# GPS_radiologger_v19_LoRa_only.net
KiCad netlist of a schematic drawn in EAGLE
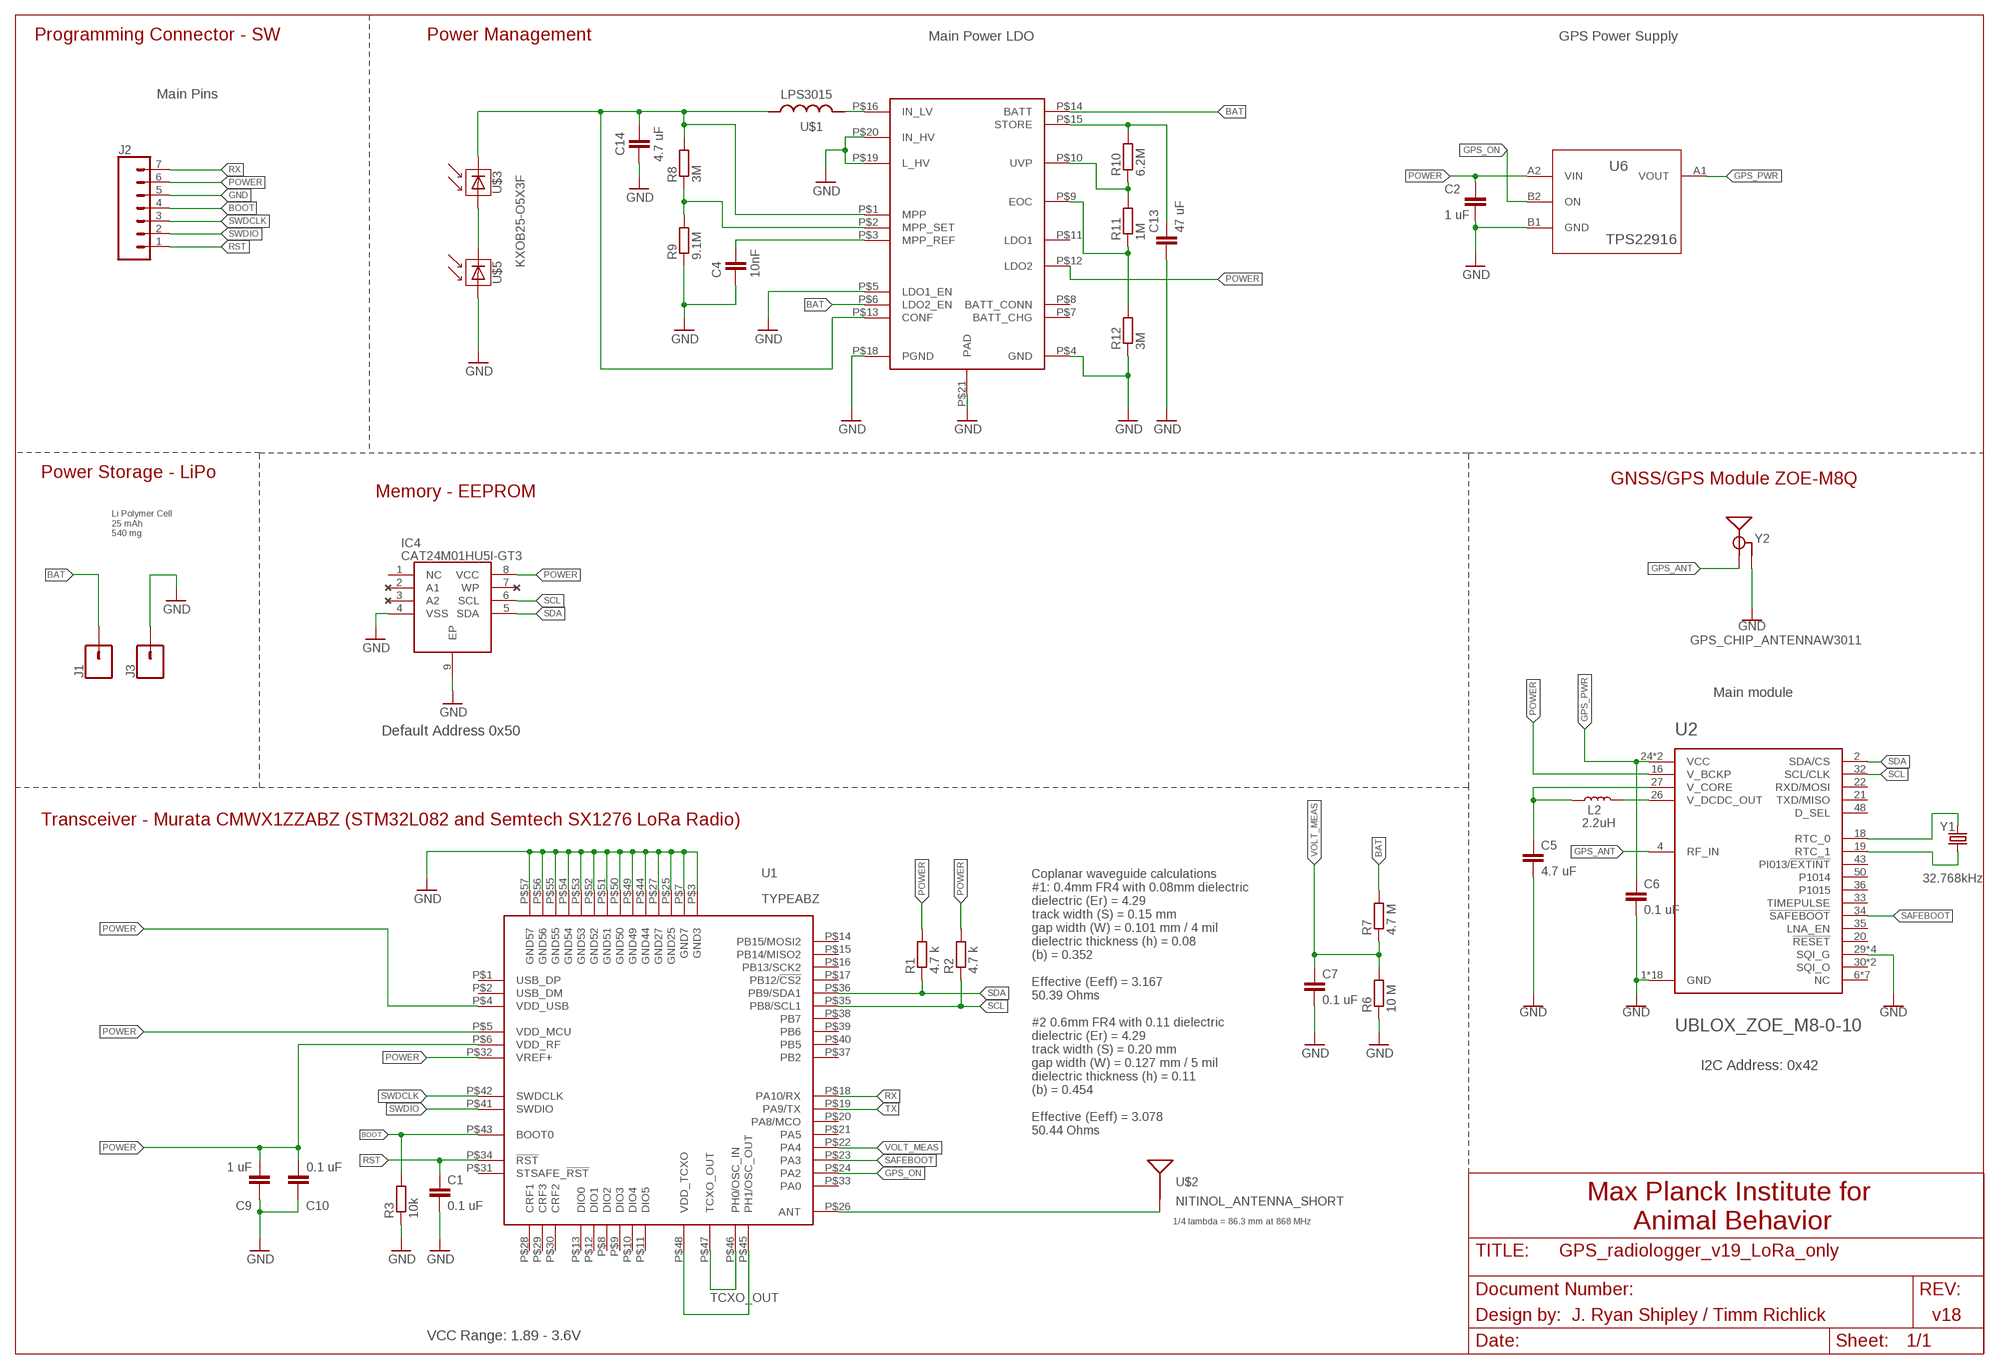
[diagram p0: schematic, sheet 1]

(export (version "E")
  (design (tool "Eeschema 10.0.6"))
  (components
    (comp (ref "C1")
      (value "0.1 uF")
      (footprint "eagle-import:C0201")
      (libsource (lib "eagle-import") (part "C-EUC0201"))
    )
    (comp (ref "C2")
      (value "1 uF")
      (footprint "eagle-import:C0201")
      (libsource (lib "eagle-import") (part "C-EUC0201"))
    )
    (comp (ref "C4")
      (value "10nF")
      (footprint "eagle-import:C0201")
      (libsource (lib "eagle-import") (part "C-EUC0201"))
    )
    (comp (ref "C5")
      (value "4.7 uF")
      (footprint "eagle-import:C0201")
      (libsource (lib "eagle-import") (part "C-EUC0201"))
    )
    (comp (ref "C6")
      (value "0.1 uF")
      (footprint "eagle-import:C0201")
      (libsource (lib "eagle-import") (part "C-EUC0201"))
    )
    (comp (ref "C7")
      (value "0.1 uF")
      (footprint "eagle-import:C0201")
      (libsource (lib "eagle-import") (part "C-EUC0201"))
    )
    (comp (ref "C9")
      (value "1 uF")
      (footprint "eagle-import:C0201")
      (libsource (lib "eagle-import") (part "C-EUC0201"))
    )
    (comp (ref "C10")
      (value "0.1 uF")
      (footprint "eagle-import:C0201")
      (libsource (lib "eagle-import") (part "C-EUC0201"))
    )
    (comp (ref "C13")
      (value "47 uF")
      (footprint "eagle-import:C0805K")
      (libsource (lib "eagle-import") (part "C-EUC0805K"))
    )
    (comp (ref "C14")
      (value "4.7 uF")
      (footprint "eagle-import:C0201")
      (libsource (lib "eagle-import") (part "C-EUC0201"))
    )
    (comp (ref "IC4")
      (value "CAT24M01HU5I-GT3")
      (footprint "eagle-import:SON50P300X200X55-9N")
      (fields
        (field (name "MOUSER_PART_NUMBER") "863-CAT24M01HU5I-GT3")
        (field (name "RS_PART_NUMBER") "7814831P")
      )
      (libsource (lib "eagle-import") (part "CAT24M01HU5I-GT3"))
    )
    (comp (ref "J1")
      (value "CONN_01PTH_NO_SILK_YES_STOP")
      (footprint "eagle-import:1X01_NO_SILK")
      (libsource (lib "eagle-import") (part "CONN_01PTH_NO_SILK_YES_STOP"))
    )
    (comp (ref "J2")
      (value "CONN_07NO_SILK")
      (footprint "eagle-import:1X07_NO_SILK")
      (libsource (lib "eagle-import") (part "CONN_07NO_SILK"))
    )
    (comp (ref "J3")
      (value "CONN_01PTH_NO_SILK_YES_STOP")
      (footprint "eagle-import:1X01_NO_SILK")
      (libsource (lib "eagle-import") (part "CONN_01PTH_NO_SILK_YES_STOP"))
    )
    (comp (ref "L2")
      (value "2.2uH")
      (footprint "eagle-import:0806")
      (libsource (lib "eagle-import") (part "2.2μH_SHIELDED_INDUCTOR"))
    )
    (comp (ref "R1")
      (value "4.7 k")
      (footprint "eagle-import:R0201")
      (libsource (lib "eagle-import") (part "R-EU_R0201"))
    )
    (comp (ref "R2")
      (value "4.7 k")
      (footprint "eagle-import:R0201")
      (libsource (lib "eagle-import") (part "R-EU_R0201"))
    )
    (comp (ref "R3")
      (value "10k")
      (footprint "eagle-import:R0201")
      (libsource (lib "eagle-import") (part "R-EU_R0201"))
    )
    (comp (ref "R6")
      (value "10 M")
      (footprint "eagle-import:R0201")
      (libsource (lib "eagle-import") (part "R-EU_R0201"))
    )
    (comp (ref "R7")
      (value "4.7 M")
      (footprint "eagle-import:R0201")
      (libsource (lib "eagle-import") (part "R-EU_R0201"))
    )
    (comp (ref "R8")
      (value "3M")
      (footprint "eagle-import:R0201")
      (libsource (lib "eagle-import") (part "R-EU_R0201"))
    )
    (comp (ref "R9")
      (value "9.1M")
      (footprint "eagle-import:R0201")
      (libsource (lib "eagle-import") (part "R-EU_R0201"))
    )
    (comp (ref "R10")
      (value "6.2M")
      (footprint "eagle-import:R0201")
      (libsource (lib "eagle-import") (part "R-EU_R0201"))
    )
    (comp (ref "R11")
      (value "1M")
      (footprint "eagle-import:R0201")
      (libsource (lib "eagle-import") (part "R-EU_R0201"))
    )
    (comp (ref "R12")
      (value "3M")
      (footprint "eagle-import:R0201")
      (libsource (lib "eagle-import") (part "R-EU_R0201"))
    )
    (comp (ref "U$1")
      (value "LPS3015")
      (footprint "eagle-import:LPS_3015")
      (libsource (lib "eagle-import") (part "LPS3015"))
    )
    (comp (ref "U$2")
      (value "NITINOL_ANTENNA_SHORT")
      (footprint "eagle-import:ICARUS_NITINOL_ANTENNA_SHORT")
      (libsource (lib "eagle-import") (part "NITINOL_ANTENNA_SHORT"))
    )
    (comp (ref "U$3")
      (value "KXOB25-O5X3F")
      (footprint "eagle-import:KXOB25-05X3F")
      (libsource (lib "eagle-import") (part "KXOB25-O5X3F"))
    )
    (comp (ref "U$5")
      (value "KXOB25-O5X3F")
      (footprint "eagle-import:KXOB25-05X3F")
      (libsource (lib "eagle-import") (part "KXOB25-O5X3F"))
    )
    (comp (ref "U1")
      (value "TYPEABZ")
      (footprint "eagle-import:TYPEABZ")
      (libsource (lib "eagle-import") (part "TYPEABZ"))
    )
    (comp (ref "U2")
      (value "UBLOX_ZOE_M8-0-10")
      (footprint "eagle-import:UBLOX_ZOE_M8-0-10")
      (libsource (lib "eagle-import") (part "UBLOX_ZOE_M8-0-10"))
    )
    (comp (ref "U4")
      (value "SPV1050")
      (footprint "eagle-import:SPV1050")
      (libsource (lib "eagle-import") (part "SPV1050"))
    )
    (comp (ref "U6")
      (value "TPS22916")
      (footprint "eagle-import:TPS22916")
      (fields (field (name "MF") "Texas Instruments") (field (name "MP") "LP5900TL-3.0"))
      (libsource (lib "eagle-import") (part "TPS22916"))
    )
    (comp (ref "Y1")
      (value "32.768kHz")
      (footprint "eagle-import:CRYSTAL-SMD-3.2X1.5MM")
      (libsource (lib "eagle-import") (part "CRYSTAL-32.768KHZSMD-3.2X1.5"))
    )
    (comp (ref "Y2")
      (value "GPS_CHIP_ANTENNAW3011")
      (footprint "eagle-import:W3011")
      (libsource (lib "eagle-import") (part "GPS_CHIP_ANTENNAW3011"))
    )
  )
  (nets
    (net (code "1") (name "/TCXO_OUT") (class "Default")
      (node (ref "U1") (pin "P$46") (pinfunction "PH0/OSC_IN_P$46") (pintype "bidirectional"))
      (node (ref "U1") (pin "P$47") (pinfunction "TCXO_OUT_P$47") (pintype "bidirectional"))
    )
    (net (code "2") (name "BAT") (class "Default")
      (node (ref "J1") (pin "1") (pinfunction "1_1") (pintype "passive"))
      (node (ref "R7") (pin "2") (pinfunction "2_2") (pintype "passive"))
      (node (ref "U4") (pin "P$14") (pinfunction "BATT_P$14") (pintype "bidirectional"))
      (node (ref "U4") (pin "P$6") (pinfunction "LDO2_EN_P$6") (pintype "input"))
    )
    (net (code "3") (name "BOOT") (class "Default")
      (node (ref "J2") (pin "4") (pinfunction "4_4") (pintype "passive"))
      (node (ref "R3") (pin "2") (pinfunction "2_2") (pintype "passive"))
      (node (ref "U1") (pin "P$43") (pinfunction "BOOT0_P$43") (pintype "bidirectional"))
    )
    (net (code "4") (name "GND") (class "Default")
      (node (ref "C1") (pin "2") (pinfunction "2_2") (pintype "passive"))
      (node (ref "C10") (pin "1") (pinfunction "1_1") (pintype "passive"))
      (node (ref "C13") (pin "2") (pinfunction "2_2") (pintype "passive"))
      (node (ref "C14") (pin "2") (pinfunction "2_2") (pintype "passive"))
      (node (ref "C2") (pin "2") (pinfunction "2_2") (pintype "passive"))
      (node (ref "C4") (pin "2") (pinfunction "2_2") (pintype "passive"))
      (node (ref "C5") (pin "2") (pinfunction "2_2") (pintype "passive"))
      (node (ref "C6") (pin "2") (pinfunction "2_2") (pintype "passive"))
      (node (ref "C7") (pin "2") (pinfunction "2_2") (pintype "passive"))
      (node (ref "C9") (pin "1") (pinfunction "1_1") (pintype "passive"))
      (node (ref "IC4") (pin "4") (pinfunction "VSS_4") (pintype "power_in"))
      (node (ref "IC4") (pin "9") (pinfunction "EP_9") (pintype "bidirectional"))
      (node (ref "J2") (pin "5") (pinfunction "5_5") (pintype "passive"))
      (node (ref "J3") (pin "1") (pinfunction "1_1") (pintype "passive"))
      (node (ref "R12") (pin "1") (pinfunction "1_1") (pintype "passive"))
      (node (ref "R3") (pin "1") (pinfunction "1_1") (pintype "passive"))
      (node (ref "R6") (pin "1") (pinfunction "1_1") (pintype "passive"))
      (node (ref "R9") (pin "1") (pinfunction "1_1") (pintype "passive"))
      (node (ref "U$5") (pin "P$2") (pinfunction "MINUS_P$2") (pintype "passive"))
      (node (ref "U1") (pin "P$25") (pinfunction "GND25_P$25") (pintype "power_in"))
      (node (ref "U1") (pin "P$27") (pinfunction "GND27_P$27") (pintype "power_in"))
      (node (ref "U1") (pin "P$3") (pinfunction "GND3_P$3") (pintype "power_in"))
      (node (ref "U1") (pin "P$44") (pinfunction "GND44_P$44") (pintype "power_in"))
      (node (ref "U1") (pin "P$49") (pinfunction "GND49_P$49") (pintype "power_in"))
      (node (ref "U1") (pin "P$50") (pinfunction "GND50_P$50") (pintype "power_in"))
      (node (ref "U1") (pin "P$51") (pinfunction "GND51_P$51") (pintype "power_in"))
      (node (ref "U1") (pin "P$52") (pinfunction "GND52_P$52") (pintype "power_in"))
      (node (ref "U1") (pin "P$53") (pinfunction "GND53_P$53") (pintype "power_in"))
      (node (ref "U1") (pin "P$54") (pinfunction "GND54_P$54") (pintype "power_in"))
      (node (ref "U1") (pin "P$55") (pinfunction "GND55_P$55") (pintype "power_in"))
      (node (ref "U1") (pin "P$56") (pinfunction "GND56_P$56") (pintype "power_in"))
      (node (ref "U1") (pin "P$57") (pinfunction "GND57_P$57") (pintype "power_in"))
      (node (ref "U1") (pin "P$7") (pinfunction "GND7_P$7") (pintype "power_in"))
      (node (ref "U2") (pin "1") (pinfunction "GND_1") (pintype "power_in"))
      (node (ref "U2") (pin "10") (pinfunction "GND_10") (pintype "power_in"))
      (node (ref "U2") (pin "11") (pinfunction "GND_11") (pintype "power_in"))
      (node (ref "U2") (pin "12") (pinfunction "GND_12") (pintype "power_in"))
      (node (ref "U2") (pin "17") (pinfunction "GND_17") (pintype "power_in"))
      (node (ref "U2") (pin "23") (pinfunction "GND_23") (pintype "power_in"))
      (node (ref "U2") (pin "29") (pinfunction "SQI_G_29") (pintype "bidirectional"))
      (node (ref "U2") (pin "3") (pinfunction "GND_3") (pintype "power_in"))
      (node (ref "U2") (pin "31") (pinfunction "SQI_G_31") (pintype "bidirectional"))
      (node (ref "U2") (pin "37") (pinfunction "GND_37") (pintype "power_in"))
      (node (ref "U2") (pin "38") (pinfunction "GND_38") (pintype "power_in"))
      (node (ref "U2") (pin "39") (pinfunction "GND_39") (pintype "power_in"))
      (node (ref "U2") (pin "40") (pinfunction "GND_40") (pintype "power_in"))
      (node (ref "U2") (pin "41") (pinfunction "GND_41") (pintype "power_in"))
      (node (ref "U2") (pin "44") (pinfunction "GND_44") (pintype "power_in"))
      (node (ref "U2") (pin "46") (pinfunction "SQI_G_46") (pintype "bidirectional"))
      (node (ref "U2") (pin "47") (pinfunction "SQI_G_47") (pintype "bidirectional"))
      (node (ref "U2") (pin "49") (pinfunction "GND_49") (pintype "power_in"))
      (node (ref "U2") (pin "5") (pinfunction "GND_5") (pintype "power_in"))
      (node (ref "U2") (pin "7") (pinfunction "GND_7") (pintype "power_in"))
      (node (ref "U2") (pin "8") (pinfunction "GND_8") (pintype "power_in"))
      (node (ref "U2") (pin "9") (pinfunction "GND_9") (pintype "power_in"))
      (node (ref "U4") (pin "P$18") (pinfunction "PGND_P$18") (pintype "power_in"))
      (node (ref "U4") (pin "P$19") (pinfunction "L_HV_P$19") (pintype "power_in"))
      (node (ref "U4") (pin "P$20") (pinfunction "IN_HV_P$20") (pintype "power_in"))
      (node (ref "U4") (pin "P$21") (pinfunction "PAD_P$21") (pintype "power_in"))
      (node (ref "U4") (pin "P$4") (pinfunction "GND_P$4") (pintype "power_in"))
      (node (ref "U4") (pin "P$5") (pinfunction "LDO1_EN_P$5") (pintype "input"))
      (node (ref "U6") (pin "B1") (pinfunction "GND_B1") (pintype "passive"))
      (node (ref "Y2") (pin "2") (pinfunction "GND_2") (pintype "bidirectional"))
      (node (ref "Y2") (pin "3") (pinfunction "GND_3") (pintype "bidirectional"))
    )
    (net (code "5") (name "GPS_ANT") (class "Default")
      (node (ref "U2") (pin "4") (pinfunction "RF_IN_4") (pintype "bidirectional"))
      (node (ref "Y2") (pin "1") (pinfunction "SIGNAL_1") (pintype "bidirectional"))
    )
    (net (code "6") (name "GPS_ON") (class "Default")
      (node (ref "U1") (pin "P$24") (pinfunction "PA2_P$24") (pintype "bidirectional"))
      (node (ref "U6") (pin "B2") (pinfunction "ON_B2") (pintype "input"))
    )
    (net (code "7") (name "GPS_PWR") (class "Default")
      (node (ref "C6") (pin "1") (pinfunction "1_1") (pintype "passive"))
      (node (ref "U2") (pin "24") (pinfunction "VCC_24") (pintype "power_in"))
      (node (ref "U2") (pin "25") (pinfunction "VCC_25") (pintype "power_in"))
      (node (ref "U6") (pin "A1") (pinfunction "VOUT_A1") (pintype "output"))
    )
    (net (code "8") (name "Net-(U$1-1)") (class "Default")
      (node (ref "C14") (pin "1") (pinfunction "1_1") (pintype "passive"))
      (node (ref "R8") (pin "2") (pinfunction "2_2") (pintype "passive"))
      (node (ref "U$1") (pin "P$1") (pinfunction "1_P$1") (pintype "passive"))
      (node (ref "U$3") (pin "P$1") (pinfunction "PLUS_P$1") (pintype "passive"))
      (node (ref "U4") (pin "P$1") (pinfunction "MPP_P$1") (pintype "input"))
      (node (ref "U4") (pin "P$13") (pinfunction "CONF_P$13") (pintype "input"))
    )
    (net (code "9") (name "Net-(U$1-2)") (class "Default")
      (node (ref "U$1") (pin "P$2") (pinfunction "2_P$2") (pintype "passive"))
      (node (ref "U4") (pin "P$16") (pinfunction "IN_LV_P$16") (pintype "power_in"))
    )
    (net (code "10") (name "Net-(U$3-MINUS)") (class "Default")
      (node (ref "U$3") (pin "P$2") (pinfunction "MINUS_P$2") (pintype "passive"))
      (node (ref "U$5") (pin "P$1") (pinfunction "PLUS_P$1") (pintype "passive"))
    )
    (net (code "11") (name "Net-(U1-ANT)") (class "Default")
      (node (ref "U$2") (pin "1") (pinfunction "SIGNAL_1") (pintype "bidirectional"))
      (node (ref "U$2") (pin "2") (pinfunction "SIGNAL_2") (pintype "bidirectional"))
      (node (ref "U$2") (pin "3") (pinfunction "SIGNAL_3") (pintype "bidirectional"))
      (node (ref "U1") (pin "P$26") (pinfunction "ANT_P$26") (pintype "bidirectional"))
    )
    (net (code "12") (name "Net-(U1-PH1{slash}OSC_OUT)") (class "Default")
      (node (ref "U1") (pin "P$45") (pinfunction "PH1/OSC_OUT_P$45") (pintype "bidirectional"))
      (node (ref "U1") (pin "P$48") (pinfunction "VDD_TCXO_P$48") (pintype "power_in"))
    )
    (net (code "13") (name "Net-(U2-RTC_0)") (class "Default")
      (node (ref "U2") (pin "18") (pinfunction "RTC_0_18") (pintype "bidirectional"))
      (node (ref "Y1") (pin "P$2") (pinfunction "2_P$2") (pintype "passive"))
    )
    (net (code "14") (name "Net-(U2-RTC_1)") (class "Default")
      (node (ref "U2") (pin "19") (pinfunction "RTC_1_19") (pintype "bidirectional"))
      (node (ref "Y1") (pin "P$1") (pinfunction "1_P$1") (pintype "passive"))
    )
    (net (code "15") (name "Net-(U2-V_CORE)") (class "Default")
      (node (ref "C5") (pin "1") (pinfunction "1_1") (pintype "passive"))
      (node (ref "L2") (pin "1") (pinfunction "1_1") (pintype "passive"))
      (node (ref "U2") (pin "27") (pinfunction "V_CORE_27") (pintype "power_in"))
    )
    (net (code "16") (name "Net-(U2-V_DCDC_OUT)") (class "Default")
      (node (ref "L2") (pin "2") (pinfunction "2_2") (pintype "passive"))
      (node (ref "U2") (pin "26") (pinfunction "V_DCDC_OUT_26") (pintype "power_in"))
    )
    (net (code "17") (name "Net-(U4-EOC)") (class "Default")
      (node (ref "R11") (pin "1") (pinfunction "1_1") (pintype "passive"))
      (node (ref "R12") (pin "2") (pinfunction "2_2") (pintype "passive"))
      (node (ref "U4") (pin "P$9") (pinfunction "EOC_P$9") (pintype "input"))
    )
    (net (code "18") (name "Net-(U4-MPP_REF)") (class "Default")
      (node (ref "C4") (pin "1") (pinfunction "1_1") (pintype "passive"))
      (node (ref "U4") (pin "P$3") (pinfunction "MPP_REF_P$3") (pintype "input"))
    )
    (net (code "19") (name "Net-(U4-MPP_SET)") (class "Default")
      (node (ref "R8") (pin "1") (pinfunction "1_1") (pintype "passive"))
      (node (ref "R9") (pin "2") (pinfunction "2_2") (pintype "passive"))
      (node (ref "U4") (pin "P$2") (pinfunction "MPP_SET_P$2") (pintype "input"))
    )
    (net (code "20") (name "Net-(U4-STORE)") (class "Default")
      (node (ref "C13") (pin "1") (pinfunction "1_1") (pintype "passive"))
      (node (ref "R10") (pin "2") (pinfunction "2_2") (pintype "passive"))
      (node (ref "U4") (pin "P$15") (pinfunction "STORE_P$15") (pintype "bidirectional"))
    )
    (net (code "21") (name "Net-(U4-UVP)") (class "Default")
      (node (ref "R10") (pin "1") (pinfunction "1_1") (pintype "passive"))
      (node (ref "R11") (pin "2") (pinfunction "2_2") (pintype "passive"))
      (node (ref "U4") (pin "P$10") (pinfunction "UVP_P$10") (pintype "input"))
    )
    (net (code "22") (name "POWER") (class "Default")
      (node (ref "C10") (pin "2") (pinfunction "2_2") (pintype "passive"))
      (node (ref "C2") (pin "1") (pinfunction "1_1") (pintype "passive"))
      (node (ref "C9") (pin "2") (pinfunction "2_2") (pintype "passive"))
      (node (ref "IC4") (pin "8") (pinfunction "VCC_8") (pintype "power_in"))
      (node (ref "J2") (pin "6") (pinfunction "6_6") (pintype "passive"))
      (node (ref "R1") (pin "2") (pinfunction "2_2") (pintype "passive"))
      (node (ref "R2") (pin "2") (pinfunction "2_2") (pintype "passive"))
      (node (ref "U1") (pin "P$32") (pinfunction "VREF+_P$32") (pintype "power_in"))
      (node (ref "U1") (pin "P$4") (pinfunction "VDD_USB_P$4") (pintype "power_in"))
      (node (ref "U1") (pin "P$5") (pinfunction "VDD_MCU_P$5") (pintype "power_in"))
      (node (ref "U1") (pin "P$6") (pinfunction "VDD_RF_P$6") (pintype "power_in"))
      (node (ref "U2") (pin "16") (pinfunction "V_BCKP_16") (pintype "power_in"))
      (node (ref "U4") (pin "P$12") (pinfunction "LDO2_P$12") (pintype "output"))
      (node (ref "U6") (pin "A2") (pinfunction "VIN_A2") (pintype "power_in"))
    )
    (net (code "23") (name "RST") (class "Default")
      (node (ref "C1") (pin "1") (pinfunction "1_1") (pintype "passive"))
      (node (ref "J2") (pin "1") (pinfunction "1_1") (pintype "passive"))
      (node (ref "U1") (pin "P$34") (pinfunction "~{RST}_P$34") (pintype "bidirectional"))
    )
    (net (code "24") (name "RX") (class "Default")
      (node (ref "J2") (pin "7") (pinfunction "7_7") (pintype "passive"))
      (node (ref "U1") (pin "P$18") (pinfunction "PA10/RX_P$18") (pintype "bidirectional"))
    )
    (net (code "25") (name "SAFEBOOT") (class "Default")
      (node (ref "U1") (pin "P$23") (pinfunction "PA3_P$23") (pintype "bidirectional"))
      (node (ref "U2") (pin "34") (pinfunction "~{SAFEBOOT}_34") (pintype "bidirectional"))
    )
    (net (code "26") (name "SCL") (class "Default")
      (node (ref "IC4") (pin "6") (pinfunction "SCL_6") (pintype "bidirectional"))
      (node (ref "R2") (pin "1") (pinfunction "1_1") (pintype "passive"))
      (node (ref "U1") (pin "P$35") (pinfunction "PB8/SCL1_P$35") (pintype "bidirectional"))
      (node (ref "U2") (pin "32") (pinfunction "SCL/CLK_32") (pintype "bidirectional"))
    )
    (net (code "27") (name "SDA") (class "Default")
      (node (ref "IC4") (pin "5") (pinfunction "SDA_5") (pintype "bidirectional"))
      (node (ref "R1") (pin "1") (pinfunction "1_1") (pintype "passive"))
      (node (ref "U1") (pin "P$36") (pinfunction "PB9/SDA1_P$36") (pintype "bidirectional"))
      (node (ref "U2") (pin "2") (pinfunction "SDA/CS_2") (pintype "bidirectional"))
    )
    (net (code "28") (name "SWDCLK") (class "Default")
      (node (ref "J2") (pin "3") (pinfunction "3_3") (pintype "passive"))
      (node (ref "U1") (pin "P$42") (pinfunction "SWDCLK_P$42") (pintype "bidirectional"))
    )
    (net (code "29") (name "SWDIO") (class "Default")
      (node (ref "J2") (pin "2") (pinfunction "2_2") (pintype "passive"))
      (node (ref "U1") (pin "P$41") (pinfunction "SWDIO_P$41") (pintype "bidirectional"))
    )
    (net (code "30") (name "TX") (class "Default")
      (node (ref "U1") (pin "P$19") (pinfunction "PA9/TX_P$19") (pintype "bidirectional"))
    )
    (net (code "31") (name "VOLT_MEAS") (class "Default")
      (node (ref "C7") (pin "1") (pinfunction "1_1") (pintype "passive"))
      (node (ref "R6") (pin "2") (pinfunction "2_2") (pintype "passive"))
      (node (ref "R7") (pin "1") (pinfunction "1_1") (pintype "passive"))
      (node (ref "U1") (pin "P$22") (pinfunction "PA4_P$22") (pintype "bidirectional"))
    )
    (net (code "32") (name "unconnected-(IC4-A1-Pad2)") (class "Default")
      (node (ref "IC4") (pin "2") (pinfunction "A1_2") (pintype "bidirectional"))
    )
    (net (code "33") (name "unconnected-(IC4-A2-Pad3)") (class "Default")
      (node (ref "IC4") (pin "3") (pinfunction "A2_3") (pintype "bidirectional"))
    )
    (net (code "34") (name "unconnected-(IC4-NC-Pad1)") (class "Default")
      (node (ref "IC4") (pin "1") (pinfunction "NC_1") (pintype "no_connect"))
    )
    (net (code "35") (name "unconnected-(IC4-WP-Pad7)") (class "Default")
      (node (ref "IC4") (pin "7") (pinfunction "WP_7") (pintype "bidirectional"))
    )
    (net (code "36") (name "unconnected-(U1-CRF1-PadP$28)") (class "Default")
      (node (ref "U1") (pin "P$28") (pinfunction "CRF1_P$28") (pintype "no_connect"))
    )
    (net (code "37") (name "unconnected-(U1-CRF2-PadP$30)") (class "Default")
      (node (ref "U1") (pin "P$30") (pinfunction "CRF2_P$30") (pintype "no_connect"))
    )
    (net (code "38") (name "unconnected-(U1-CRF3-PadP$29)") (class "Default")
      (node (ref "U1") (pin "P$29") (pinfunction "CRF3_P$29") (pintype "no_connect"))
    )
    (net (code "39") (name "unconnected-(U1-DIO0-PadP$13)") (class "Default")
      (node (ref "U1") (pin "P$13") (pinfunction "DIO0_P$13") (pintype "no_connect"))
    )
    (net (code "40") (name "unconnected-(U1-DIO1-PadP$12)") (class "Default")
      (node (ref "U1") (pin "P$12") (pinfunction "DIO1_P$12") (pintype "no_connect"))
    )
    (net (code "41") (name "unconnected-(U1-DIO2-PadP$8)") (class "Default")
      (node (ref "U1") (pin "P$8") (pinfunction "DIO2_P$8") (pintype "no_connect"))
    )
    (net (code "42") (name "unconnected-(U1-DIO3-PadP$9)") (class "Default")
      (node (ref "U1") (pin "P$9") (pinfunction "DIO3_P$9") (pintype "no_connect"))
    )
    (net (code "43") (name "unconnected-(U1-DIO4-PadP$10)") (class "Default")
      (node (ref "U1") (pin "P$10") (pinfunction "DIO4_P$10") (pintype "bidirectional"))
    )
    (net (code "44") (name "unconnected-(U1-DIO5-PadP$11)") (class "Default")
      (node (ref "U1") (pin "P$11") (pinfunction "DIO5_P$11") (pintype "bidirectional"))
    )
    (net (code "45") (name "unconnected-(U1-PA0-PadP$33)") (class "Default")
      (node (ref "U1") (pin "P$33") (pinfunction "PA0_P$33") (pintype "bidirectional"))
    )
    (net (code "46") (name "unconnected-(U1-PA5-PadP$21)") (class "Default")
      (node (ref "U1") (pin "P$21") (pinfunction "PA5_P$21") (pintype "bidirectional"))
    )
    (net (code "47") (name "unconnected-(U1-PA8{slash}MCO-PadP$20)") (class "Default")
      (node (ref "U1") (pin "P$20") (pinfunction "PA8/MCO_P$20") (pintype "bidirectional"))
    )
    (net (code "48") (name "unconnected-(U1-PB2-PadP$37)") (class "Default")
      (node (ref "U1") (pin "P$37") (pinfunction "PB2_P$37") (pintype "bidirectional"))
    )
    (net (code "49") (name "unconnected-(U1-PB5-PadP$40)") (class "Default")
      (node (ref "U1") (pin "P$40") (pinfunction "PB5_P$40") (pintype "bidirectional"))
    )
    (net (code "50") (name "unconnected-(U1-PB6-PadP$39)") (class "Default")
      (node (ref "U1") (pin "P$39") (pinfunction "PB6_P$39") (pintype "bidirectional"))
    )
    (net (code "51") (name "unconnected-(U1-PB7-PadP$38)") (class "Default")
      (node (ref "U1") (pin "P$38") (pinfunction "PB7_P$38") (pintype "bidirectional"))
    )
    (net (code "52") (name "unconnected-(U1-PB12{slash}~{CS2}-PadP$17)") (class "Default")
      (node (ref "U1") (pin "P$17") (pinfunction "PB12/~{CS2}_P$17") (pintype "bidirectional"))
    )
    (net (code "53") (name "unconnected-(U1-PB13{slash}SCK2-PadP$16)") (class "Default")
      (node (ref "U1") (pin "P$16") (pinfunction "PB13/SCK2_P$16") (pintype "bidirectional"))
    )
    (net (code "54") (name "unconnected-(U1-PB14{slash}MISO2-PadP$15)") (class "Default")
      (node (ref "U1") (pin "P$15") (pinfunction "PB14/MISO2_P$15") (pintype "bidirectional"))
    )
    (net (code "55") (name "unconnected-(U1-PB15{slash}MOSI2-PadP$14)") (class "Default")
      (node (ref "U1") (pin "P$14") (pinfunction "PB15/MOSI2_P$14") (pintype "bidirectional"))
    )
    (net (code "56") (name "unconnected-(U1-STSAFE_~{RST}-PadP$31)") (class "Default")
      (node (ref "U1") (pin "P$31") (pinfunction "STSAFE_~{RST}_P$31") (pintype "bidirectional"))
    )
    (net (code "57") (name "unconnected-(U1-USB_DM-PadP$2)") (class "Default")
      (node (ref "U1") (pin "P$2") (pinfunction "USB_DM_P$2") (pintype "bidirectional"))
    )
    (net (code "58") (name "unconnected-(U1-USB_DP-PadP$1)") (class "Default")
      (node (ref "U1") (pin "P$1") (pinfunction "USB_DP_P$1") (pintype "bidirectional"))
    )
    (net (code "59") (name "unconnected-(U2-D_SEL-Pad48)") (class "Default")
      (node (ref "U2") (pin "48") (pinfunction "D_SEL_48") (pintype "bidirectional"))
    )
    (net (code "60") (name "unconnected-(U2-LNA_EN-Pad35)") (class "Default")
      (node (ref "U2") (pin "35") (pinfunction "LNA_EN_35") (pintype "bidirectional"))
    )
    (net (code "61") (name "unconnected-(U2-NC-Pad6)") (class "Default")
      (node (ref "U2") (pin "6") (pinfunction "NC_6") (pintype "no_connect"))
    )
    (net (code "62") (name "unconnected-(U2-NC-Pad13)") (class "Default")
      (node (ref "U2") (pin "13") (pinfunction "NC_13") (pintype "no_connect"))
    )
    (net (code "63") (name "unconnected-(U2-NC-Pad14)") (class "Default")
      (node (ref "U2") (pin "14") (pinfunction "NC_14") (pintype "no_connect"))
    )
    (net (code "64") (name "unconnected-(U2-NC-Pad15)") (class "Default")
      (node (ref "U2") (pin "15") (pinfunction "NC_15") (pintype "no_connect"))
    )
    (net (code "65") (name "unconnected-(U2-NC-Pad28)") (class "Default")
      (node (ref "U2") (pin "28") (pinfunction "NC_28") (pintype "no_connect"))
    )
    (net (code "66") (name "unconnected-(U2-NC-Pad42)") (class "Default")
      (node (ref "U2") (pin "42") (pinfunction "NC_42") (pintype "no_connect"))
    )
    (net (code "67") (name "unconnected-(U2-NC-Pad51)") (class "Default")
      (node (ref "U2") (pin "51") (pinfunction "NC_51") (pintype "no_connect"))
    )
    (net (code "68") (name "unconnected-(U2-P1014-Pad50)") (class "Default")
      (node (ref "U2") (pin "50") (pinfunction "P1014_50") (pintype "bidirectional"))
    )
    (net (code "69") (name "unconnected-(U2-P1015-Pad36)") (class "Default")
      (node (ref "U2") (pin "36") (pinfunction "P1015_36") (pintype "bidirectional"))
    )
    (net (code "70") (name "unconnected-(U2-PI013{slash}~{EXTINT}-Pad43)") (class "Default")
      (node (ref "U2") (pin "43") (pinfunction "PI013/~{EXTINT}_43") (pintype "bidirectional"))
    )
    (net (code "71") (name "unconnected-(U2-RXD{slash}MOSI-Pad22)") (class "Default")
      (node (ref "U2") (pin "22") (pinfunction "RXD/MOSI_22") (pintype "bidirectional"))
    )
    (net (code "72") (name "unconnected-(U2-SQI_O-Pad30)") (class "Default")
      (node (ref "U2") (pin "30") (pinfunction "SQI_O_30") (pintype "no_connect"))
    )
    (net (code "73") (name "unconnected-(U2-SQI_O-Pad45)") (class "Default")
      (node (ref "U2") (pin "45") (pinfunction "SQI_O_45") (pintype "no_connect"))
    )
    (net (code "74") (name "unconnected-(U2-TIMEPULSE-Pad33)") (class "Default")
      (node (ref "U2") (pin "33") (pinfunction "TIMEPULSE_33") (pintype "bidirectional"))
    )
    (net (code "75") (name "unconnected-(U2-TXD{slash}MISO-Pad21)") (class "Default")
      (node (ref "U2") (pin "21") (pinfunction "TXD/MISO_21") (pintype "bidirectional"))
    )
    (net (code "76") (name "unconnected-(U2-~{RESET}-Pad20)") (class "Default")
      (node (ref "U2") (pin "20") (pinfunction "~{RESET}_20") (pintype "bidirectional"))
    )
    (net (code "77") (name "unconnected-(U4-BATT_CHG-PadP$7)") (class "Default")
      (node (ref "U4") (pin "P$7") (pinfunction "BATT_CHG_P$7") (pintype "open_collector"))
    )
    (net (code "78") (name "unconnected-(U4-BATT_CONN-PadP$8)") (class "Default")
      (node (ref "U4") (pin "P$8") (pinfunction "BATT_CONN_P$8") (pintype "open_collector"))
    )
    (net (code "79") (name "unconnected-(U4-LDO1-PadP$11)") (class "Default")
      (node (ref "U4") (pin "P$11") (pinfunction "LDO1_P$11") (pintype "output"))
    )
  )
)
